# 10_Phase.net
KiCad netlist of a schematic drawn in Altium Designer
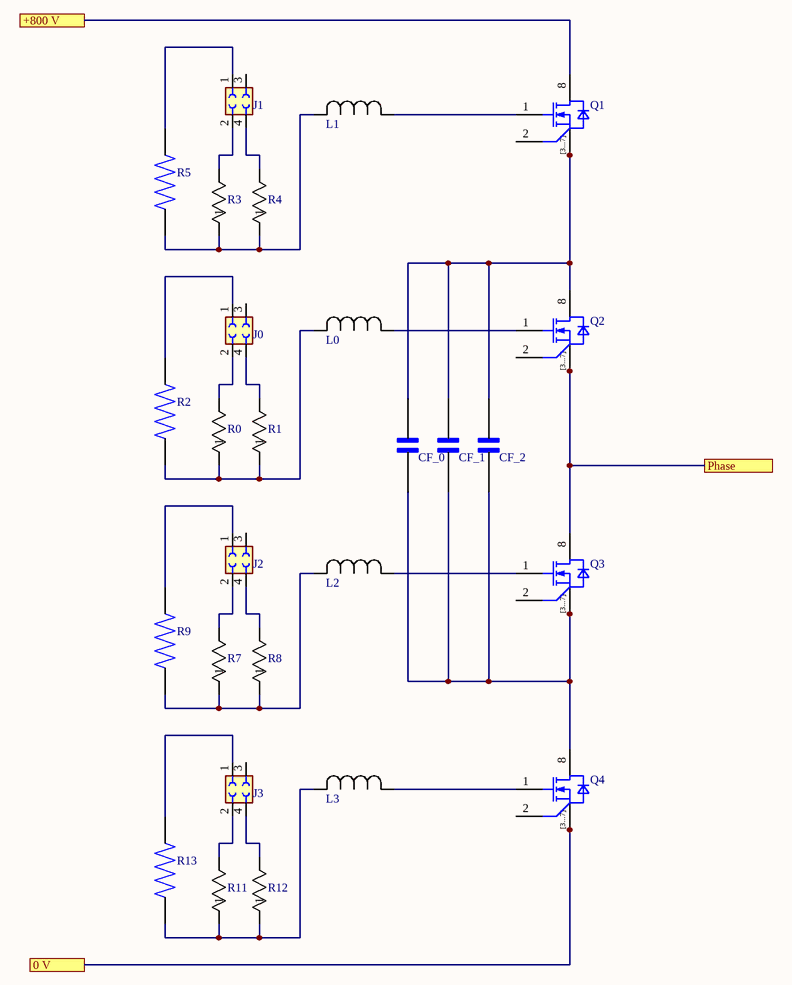
[diagram p0: 10_Phase.SchDoc]

(export (version "E")
  (design (tool "Eeschema 10.0.6"))
  (components
    (comp (ref "CF_0")
      (value "B32776Z4406K000")
      (footprint "CAP_B32776Z4406K000")
      (description "40 ÂµF Film Capacitor 500V Polypropylene (PP), Metallized Radial - 4 Leads")
      (fields (field (name "MF") "EPCOS"))
      (libsource (lib "B32776Z4406K000") (part "B32776Z4406K000"))
    )
    (comp (ref "CF_1")
      (value "B32776Z4406K000")
      (footprint "CAP_B32776Z4406K000")
      (description "40 ÂµF Film Capacitor 500V Polypropylene (PP), Metallized Radial - 4 Leads")
      (fields (field (name "MF") "EPCOS"))
      (libsource (lib "B32776Z4406K000") (part "B32776Z4406K000"))
    )
    (comp (ref "CF_2")
      (value "B32776Z4406K000")
      (footprint "CAP_B32776Z4406K000")
      (description "40 ÂµF Film Capacitor 500V Polypropylene (PP), Metallized Radial - 4 Leads")
      (fields (field (name "MF") "EPCOS"))
      (libsource (lib "B32776Z4406K000") (part "B32776Z4406K000"))
    )
    (comp (ref "J0")
      (value "6230XX21021_62300421021")
      (footprint "62300421021")
      (description "WR-PHD 1.27 mm Dual SMT Socket Header H=4.50mm")
      (fields (field (name "MF") "Wurth Elektronik") (field (name "MP") "62300421021"))
      (libsource (lib "62300421021") (part "6230XX21021_62300421021"))
    )
    (comp (ref "J1")
      (value "6230XX21021_62300421021")
      (footprint "62300421021")
      (description "WR-PHD 1.27 mm Dual SMT Socket Header H=4.50mm")
      (fields (field (name "MF") "Wurth Elektronik") (field (name "MP") "62300421021"))
      (libsource (lib "62300421021") (part "6230XX21021_62300421021"))
    )
    (comp (ref "J2")
      (value "6230XX21021_62300421021")
      (footprint "62300421021")
      (description "WR-PHD 1.27 mm Dual SMT Socket Header H=4.50mm")
      (fields (field (name "MF") "Wurth Elektronik") (field (name "MP") "62300421021"))
      (libsource (lib "62300421021") (part "6230XX21021_62300421021"))
    )
    (comp (ref "J3")
      (value "6230XX21021_62300421021")
      (footprint "62300421021")
      (description "WR-PHD 1.27 mm Dual SMT Socket Header H=4.50mm")
      (fields (field (name "MF") "Wurth Elektronik") (field (name "MP") "62300421021"))
      (libsource (lib "62300421021") (part "6230XX21021_62300421021"))
    )
    (comp (ref "L0")
      (value "MPZ2012S300AT000")
      (footprint "IND_2012_TDK")
      (description "Description")
      (fields (field (name "COPYRIGHT") "Copyright (C) 2025 Ultra Librarian. All rights reserved."))
      (libsource (lib "MPZ2012S300AT000") (part "MPZ2012S300AT000"))
    )
    (comp (ref "L1")
      (value "MPZ2012S300AT000")
      (footprint "IND_2012_TDK")
      (description "Description")
      (fields (field (name "COPYRIGHT") "Copyright (C) 2025 Ultra Librarian. All rights reserved."))
      (libsource (lib "MPZ2012S300AT000") (part "MPZ2012S300AT000"))
    )
    (comp (ref "L2")
      (value "MPZ2012S300AT000")
      (footprint "IND_2012_TDK")
      (description "Description")
      (fields (field (name "COPYRIGHT") "Copyright (C) 2025 Ultra Librarian. All rights reserved."))
      (libsource (lib "MPZ2012S300AT000") (part "MPZ2012S300AT000"))
    )
    (comp (ref "L3")
      (value "MPZ2012S300AT000")
      (footprint "IND_2012_TDK")
      (description "Description")
      (fields (field (name "COPYRIGHT") "Copyright (C) 2025 Ultra Librarian. All rights reserved."))
      (libsource (lib "MPZ2012S300AT000") (part "MPZ2012S300AT000"))
    )
    (comp (ref "Q1")
      (value "IMBG120R026M2H")
      (footprint "TO127P1500X470-8N-2-V1")
      (fields (field (name "MANUFACTURER") "Infineon Technologies"))
      (libsource (lib "IMBG120R026M2H") (part "IMBG120R026M2H"))
    )
    (comp (ref "Q2")
      (value "IMBG120R026M2H")
      (footprint "TO127P1500X470-8N-2-V1")
      (fields (field (name "MANUFACTURER") "Infineon Technologies"))
      (libsource (lib "IMBG120R026M2H") (part "IMBG120R026M2H"))
    )
    (comp (ref "Q3")
      (value "IMBG120R026M2H")
      (footprint "TO127P1500X470-8N-2-V1")
      (fields (field (name "MANUFACTURER") "Infineon Technologies"))
      (libsource (lib "IMBG120R026M2H") (part "IMBG120R026M2H"))
    )
    (comp (ref "Q4")
      (value "IMBG120R026M2H")
      (footprint "TO127P1500X470-8N-2-V1")
      (fields (field (name "MANUFACTURER") "Infineon Technologies"))
      (libsource (lib "IMBG120R026M2H") (part "IMBG120R026M2H"))
    )
    (comp (ref "R0")
      (value "HCJ1206ZT0R00")
      (footprint "RES_HCJ1206_STP")
      (description "Description")
      (fields (field (name "COPYRIGHT") "Copyright (C) 2025 Ultra Librarian. All rights reserved."))
      (libsource (lib "HCJ1206ZT0R00") (part "HCJ1206ZT0R00"))
    )
    (comp (ref "R1")
      (value "HCJ1206ZT0R00")
      (footprint "RES_HCJ1206_STP")
      (description "Description")
      (fields (field (name "COPYRIGHT") "Copyright (C) 2025 Ultra Librarian. All rights reserved."))
      (libsource (lib "HCJ1206ZT0R00") (part "HCJ1206ZT0R00"))
    )
    (comp (ref "R2")
      (value "AF0805FR-07130RL")
      (footprint "RESC2012X60N")
      (fields (field (name "MF") "Yageo"))
      (libsource (lib "AF0805FR-07130RL") (part "AF0805FR-07130RL"))
    )
    (comp (ref "R3")
      (value "HCJ1206ZT0R00")
      (footprint "RES_HCJ1206_STP")
      (description "Description")
      (fields (field (name "COPYRIGHT") "Copyright (C) 2025 Ultra Librarian. All rights reserved."))
      (libsource (lib "HCJ1206ZT0R00") (part "HCJ1206ZT0R00"))
    )
    (comp (ref "R4")
      (value "HCJ1206ZT0R00")
      (footprint "RES_HCJ1206_STP")
      (description "Description")
      (fields (field (name "COPYRIGHT") "Copyright (C) 2025 Ultra Librarian. All rights reserved."))
      (libsource (lib "HCJ1206ZT0R00") (part "HCJ1206ZT0R00"))
    )
    (comp (ref "R5")
      (value "AF0805FR-07130RL")
      (footprint "RESC2012X60N")
      (fields (field (name "MF") "Yageo"))
      (libsource (lib "AF0805FR-07130RL") (part "AF0805FR-07130RL"))
    )
    (comp (ref "R7")
      (value "HCJ1206ZT0R00")
      (footprint "RES_HCJ1206_STP")
      (description "Description")
      (fields (field (name "COPYRIGHT") "Copyright (C) 2025 Ultra Librarian. All rights reserved."))
      (libsource (lib "HCJ1206ZT0R00") (part "HCJ1206ZT0R00"))
    )
    (comp (ref "R8")
      (value "HCJ1206ZT0R00")
      (footprint "RES_HCJ1206_STP")
      (description "Description")
      (fields (field (name "COPYRIGHT") "Copyright (C) 2025 Ultra Librarian. All rights reserved."))
      (libsource (lib "HCJ1206ZT0R00") (part "HCJ1206ZT0R00"))
    )
    (comp (ref "R9")
      (value "AF0805FR-07130RL")
      (footprint "RESC2012X60N")
      (fields (field (name "MF") "Yageo"))
      (libsource (lib "AF0805FR-07130RL") (part "AF0805FR-07130RL"))
    )
    (comp (ref "R11")
      (value "HCJ1206ZT0R00")
      (footprint "RES_HCJ1206_STP")
      (description "Description")
      (fields (field (name "COPYRIGHT") "Copyright (C) 2025 Ultra Librarian. All rights reserved."))
      (libsource (lib "HCJ1206ZT0R00") (part "HCJ1206ZT0R00"))
    )
    (comp (ref "R12")
      (value "HCJ1206ZT0R00")
      (footprint "RES_HCJ1206_STP")
      (description "Description")
      (fields (field (name "COPYRIGHT") "Copyright (C) 2025 Ultra Librarian. All rights reserved."))
      (libsource (lib "HCJ1206ZT0R00") (part "HCJ1206ZT0R00"))
    )
    (comp (ref "R13")
      (value "AF0805FR-07130RL")
      (footprint "RESC2012X60N")
      (fields (field (name "MF") "Yageo"))
      (libsource (lib "AF0805FR-07130RL") (part "AF0805FR-07130RL"))
    )
  )
  (nets
    (net (code "1") (name "/+800 V") (class "Default")
      (node (ref "Q1") (pin "8") (pinfunction "DRAIN_8") (pintype "passive"))
    )
    (net (code "2") (name "/0 V") (class "Default")
      (node (ref "Q4") (pin "3") (pinfunction "SOURCE1_3") (pintype "passive"))
      (node (ref "Q4") (pin "4") (pinfunction "SOURCE2_4") (pintype "passive"))
      (node (ref "Q4") (pin "5") (pinfunction "SOURCE3_5") (pintype "passive"))
      (node (ref "Q4") (pin "6") (pinfunction "SOURCE4_6") (pintype "passive"))
      (node (ref "Q4") (pin "7") (pinfunction "SOURCE5_7") (pintype "passive"))
    )
    (net (code "3") (name "/Phase") (class "Default")
      (node (ref "Q2") (pin "3") (pinfunction "SOURCE1_3") (pintype "passive"))
      (node (ref "Q2") (pin "4") (pinfunction "SOURCE2_4") (pintype "passive"))
      (node (ref "Q2") (pin "5") (pinfunction "SOURCE3_5") (pintype "passive"))
      (node (ref "Q2") (pin "6") (pinfunction "SOURCE4_6") (pintype "passive"))
      (node (ref "Q2") (pin "7") (pinfunction "SOURCE5_7") (pintype "passive"))
      (node (ref "Q3") (pin "8") (pinfunction "DRAIN_8") (pintype "passive"))
    )
    (net (code "4") (name "Net-(J0-Pad1)") (class "Default")
      (node (ref "J0") (pin "1") (pinfunction "1_1") (pintype "passive"))
      (node (ref "R2") (pin "2") (pinfunction "2_2") (pintype "passive"))
    )
    (net (code "5") (name "Net-(J0-Pad2)") (class "Default")
      (node (ref "J0") (pin "2") (pinfunction "2_2") (pintype "passive"))
      (node (ref "R0") (pin "2") (pinfunction "2_2") (pintype "passive"))
    )
    (net (code "6") (name "Net-(J0-Pad4)") (class "Default")
      (node (ref "J0") (pin "4") (pinfunction "4_4") (pintype "passive"))
      (node (ref "R1") (pin "2") (pinfunction "2_2") (pintype "passive"))
    )
    (net (code "7") (name "Net-(J1-Pad1)") (class "Default")
      (node (ref "J1") (pin "1") (pinfunction "1_1") (pintype "passive"))
      (node (ref "R5") (pin "2") (pinfunction "2_2") (pintype "passive"))
    )
    (net (code "8") (name "Net-(J1-Pad2)") (class "Default")
      (node (ref "J1") (pin "2") (pinfunction "2_2") (pintype "passive"))
      (node (ref "R3") (pin "2") (pinfunction "2_2") (pintype "passive"))
    )
    (net (code "9") (name "Net-(J1-Pad4)") (class "Default")
      (node (ref "J1") (pin "4") (pinfunction "4_4") (pintype "passive"))
      (node (ref "R4") (pin "2") (pinfunction "2_2") (pintype "passive"))
    )
    (net (code "10") (name "Net-(J2-Pad1)") (class "Default")
      (node (ref "J2") (pin "1") (pinfunction "1_1") (pintype "passive"))
      (node (ref "R9") (pin "2") (pinfunction "2_2") (pintype "passive"))
    )
    (net (code "11") (name "Net-(J2-Pad2)") (class "Default")
      (node (ref "J2") (pin "2") (pinfunction "2_2") (pintype "passive"))
      (node (ref "R7") (pin "2") (pinfunction "2_2") (pintype "passive"))
    )
    (net (code "12") (name "Net-(J2-Pad4)") (class "Default")
      (node (ref "J2") (pin "4") (pinfunction "4_4") (pintype "passive"))
      (node (ref "R8") (pin "2") (pinfunction "2_2") (pintype "passive"))
    )
    (net (code "13") (name "Net-(J3-Pad1)") (class "Default")
      (node (ref "J3") (pin "1") (pinfunction "1_1") (pintype "passive"))
      (node (ref "R13") (pin "2") (pinfunction "2_2") (pintype "passive"))
    )
    (net (code "14") (name "Net-(J3-Pad2)") (class "Default")
      (node (ref "J3") (pin "2") (pinfunction "2_2") (pintype "passive"))
      (node (ref "R11") (pin "2") (pinfunction "2_2") (pintype "passive"))
    )
    (net (code "15") (name "Net-(J3-Pad4)") (class "Default")
      (node (ref "J3") (pin "4") (pinfunction "4_4") (pintype "passive"))
      (node (ref "R12") (pin "2") (pinfunction "2_2") (pintype "passive"))
    )
    (net (code "16") (name "Net-(L0-Pad2)") (class "Default")
      (node (ref "L0") (pin "2") (pinfunction "2_2") (pintype "passive"))
      (node (ref "R0") (pin "1") (pinfunction "1_1") (pintype "passive"))
      (node (ref "R1") (pin "1") (pinfunction "1_1") (pintype "passive"))
      (node (ref "R2") (pin "1") (pinfunction "1_1") (pintype "passive"))
    )
    (net (code "17") (name "Net-(L1-Pad2)") (class "Default")
      (node (ref "L1") (pin "2") (pinfunction "2_2") (pintype "passive"))
      (node (ref "R3") (pin "1") (pinfunction "1_1") (pintype "passive"))
      (node (ref "R4") (pin "1") (pinfunction "1_1") (pintype "passive"))
      (node (ref "R5") (pin "1") (pinfunction "1_1") (pintype "passive"))
    )
    (net (code "18") (name "Net-(L2-Pad2)") (class "Default")
      (node (ref "L2") (pin "2") (pinfunction "2_2") (pintype "passive"))
      (node (ref "R7") (pin "1") (pinfunction "1_1") (pintype "passive"))
      (node (ref "R8") (pin "1") (pinfunction "1_1") (pintype "passive"))
      (node (ref "R9") (pin "1") (pinfunction "1_1") (pintype "passive"))
    )
    (net (code "19") (name "Net-(L3-Pad2)") (class "Default")
      (node (ref "L3") (pin "2") (pinfunction "2_2") (pintype "passive"))
      (node (ref "R11") (pin "1") (pinfunction "1_1") (pintype "passive"))
      (node (ref "R12") (pin "1") (pinfunction "1_1") (pintype "passive"))
      (node (ref "R13") (pin "1") (pinfunction "1_1") (pintype "passive"))
    )
    (net (code "20") (name "Net-(Q1-GATE)") (class "Default")
      (node (ref "L1") (pin "1") (pinfunction "1_1") (pintype "passive"))
      (node (ref "Q1") (pin "1") (pinfunction "GATE_1") (pintype "passive"))
    )
    (net (code "21") (name "Net-(Q1-SOURCE1)") (class "Default")
      (node (ref "CF_0") (pin "2") (pinfunction "2_2") (pintype "passive"))
      (node (ref "CF_1") (pin "2") (pinfunction "2_2") (pintype "passive"))
      (node (ref "CF_2") (pin "2") (pinfunction "2_2") (pintype "passive"))
      (node (ref "Q1") (pin "3") (pinfunction "SOURCE1_3") (pintype "passive"))
      (node (ref "Q1") (pin "4") (pinfunction "SOURCE2_4") (pintype "passive"))
      (node (ref "Q1") (pin "5") (pinfunction "SOURCE3_5") (pintype "passive"))
      (node (ref "Q1") (pin "6") (pinfunction "SOURCE4_6") (pintype "passive"))
      (node (ref "Q1") (pin "7") (pinfunction "SOURCE5_7") (pintype "passive"))
      (node (ref "Q2") (pin "8") (pinfunction "DRAIN_8") (pintype "passive"))
    )
    (net (code "22") (name "Net-(Q2-GATE)") (class "Default")
      (node (ref "L0") (pin "1") (pinfunction "1_1") (pintype "passive"))
      (node (ref "Q2") (pin "1") (pinfunction "GATE_1") (pintype "passive"))
    )
    (net (code "23") (name "Net-(Q3-GATE)") (class "Default")
      (node (ref "L2") (pin "1") (pinfunction "1_1") (pintype "passive"))
      (node (ref "Q3") (pin "1") (pinfunction "GATE_1") (pintype "passive"))
    )
    (net (code "24") (name "Net-(Q3-SOURCE1)") (class "Default")
      (node (ref "CF_0") (pin "1") (pinfunction "1_1") (pintype "passive"))
      (node (ref "CF_1") (pin "1") (pinfunction "1_1") (pintype "passive"))
      (node (ref "CF_2") (pin "1") (pinfunction "1_1") (pintype "passive"))
      (node (ref "Q3") (pin "3") (pinfunction "SOURCE1_3") (pintype "passive"))
      (node (ref "Q3") (pin "4") (pinfunction "SOURCE2_4") (pintype "passive"))
      (node (ref "Q3") (pin "5") (pinfunction "SOURCE3_5") (pintype "passive"))
      (node (ref "Q3") (pin "6") (pinfunction "SOURCE4_6") (pintype "passive"))
      (node (ref "Q3") (pin "7") (pinfunction "SOURCE5_7") (pintype "passive"))
      (node (ref "Q4") (pin "8") (pinfunction "DRAIN_8") (pintype "passive"))
    )
    (net (code "25") (name "Net-(Q4-GATE)") (class "Default")
      (node (ref "L3") (pin "1") (pinfunction "1_1") (pintype "passive"))
      (node (ref "Q4") (pin "1") (pinfunction "GATE_1") (pintype "passive"))
    )
    (net (code "26") (name "unconnected-(J0-Pad3)") (class "Default")
      (node (ref "J0") (pin "3") (pinfunction "3_3") (pintype "passive"))
    )
    (net (code "27") (name "unconnected-(J1-Pad3)") (class "Default")
      (node (ref "J1") (pin "3") (pinfunction "3_3") (pintype "passive"))
    )
    (net (code "28") (name "unconnected-(J2-Pad3)") (class "Default")
      (node (ref "J2") (pin "3") (pinfunction "3_3") (pintype "passive"))
    )
    (net (code "29") (name "unconnected-(J3-Pad3)") (class "Default")
      (node (ref "J3") (pin "3") (pinfunction "3_3") (pintype "passive"))
    )
    (net (code "30") (name "unconnected-(Q1-SENSE-Pad2)") (class "Default")
      (node (ref "Q1") (pin "2") (pinfunction "SENSE_2") (pintype "passive"))
    )
    (net (code "31") (name "unconnected-(Q2-SENSE-Pad2)") (class "Default")
      (node (ref "Q2") (pin "2") (pinfunction "SENSE_2") (pintype "passive"))
    )
    (net (code "32") (name "unconnected-(Q3-SENSE-Pad2)") (class "Default")
      (node (ref "Q3") (pin "2") (pinfunction "SENSE_2") (pintype "passive"))
    )
    (net (code "33") (name "unconnected-(Q4-SENSE-Pad2)") (class "Default")
      (node (ref "Q4") (pin "2") (pinfunction "SENSE_2") (pintype "passive"))
    )
  )
)
